# Main.net
KiCad netlist of a schematic drawn in Altium Designer
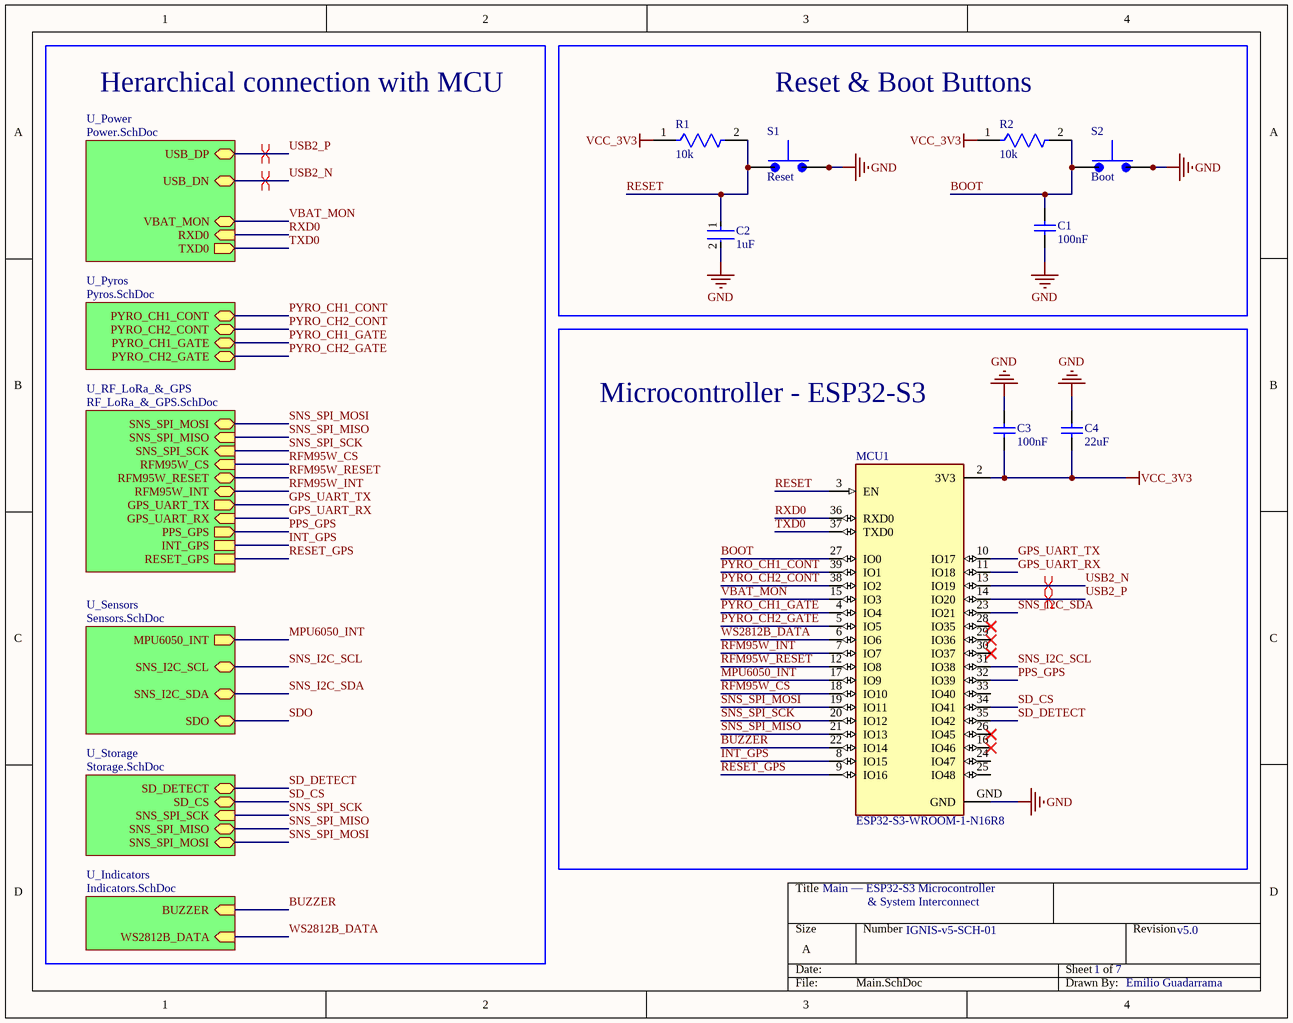
[diagram p0: Main.SchDoc]

(export (version "E")
  (design (tool "Eeschema 10.0.6"))
  (components
    (comp (ref "C1")
      (value "100nF")
      (footprint "CAPC2013X145X50NL20T25")
      (fields (field (name "MANUFACTURER") "Kemet") (field (name "PART NUMBER") "C0805S104K5RACTU"))
      (libsource (lib "Altium Content Vault") (part "CAP"))
    )
    (comp (ref "C2")
      (value "1uF")
      (footprint "FP-0805-L_2_01_0_2-W_1_25-MFG")
      (description "08051C105K4T2A Cap Ceramic 1uF 100V X7R 10% Pad SMD 0805 125C Automotive T/R")
      (fields (field (name "TOLERANCE") "10%"))
      (libsource (lib "Altium Content Vault") (part "b4654b650e69147ec39a6b967a45e02"))
    )
    (comp (ref "C3")
      (value "100nF")
      (footprint "CAPC2013X145X50NL20T25")
      (fields (field (name "MANUFACTURER") "Kemet") (field (name "PART NUMBER") "C0805S104K5RACTU"))
      (libsource (lib "Altium Content Vault") (part "CAP"))
    )
    (comp (ref "C4")
      (value "22uF")
      (footprint "CAPC0805(2012)145_L")
      (description "CAP 22uF 6.3V ±10% 0805 (2012 Metric) Thickness 1.45mm SMD")
      (fields (field (name "TOLERANCE") "Â±10%"))
      (libsource (lib "Altium Content Vault") (part "CAP"))
    )
    (comp (ref "MCU1")
      (value "ESP32-S3-WROOM-1-N16R8")
      (footprint "XCVR_ESP32-S3-WROOM-1-N16R2")
      (description "Bluetooth, WiFi 802.11b/g/n, Bluetooth v5.0 Transceiver Module 2.4GHz PCB Trace Surface Mount")
      (fields (field (name "MF") "Espressif Systems") (field (name "MP") "ESP32S3WROOM1N16R2"))
      (libsource (lib "ESP32-S3-WROOM-1-N16R8") (part "ESP32-S3-WROOM-1-N16R8"))
    )
    (comp (ref "R1")
      (value "10k")
      (footprint "FP-MCT0603-IPC_A")
      (description "RES SMD 100 OHM 1% 1/8W 0603")
      (fields (field (name "TOLERANCE") "0.1%"))
      (libsource (lib "Altium Content Vault") (part "1029c3af85768c4190bb7ad29bc67b5"))
    )
    (comp (ref "R2")
      (value "10k")
      (footprint "FP-MCT0603-IPC_A")
      (description "RES SMD 100 OHM 1% 1/8W 0603")
      (fields (field (name "TOLERANCE") "0.1%"))
      (libsource (lib "Altium Content Vault") (part "1029c3af85768c4190bb7ad29bc67b5"))
    )
    (comp (ref "S1")
      (value "Reset")
      (footprint "SW_SKRPABE010")
      (description "Switch Tactile N.O. SPST Button J-Bend 0.05A 16VDC 1.57N SMD Automotive T/R")
      (fields (field (name "MF") "ALPS") (field (name "MP") "SKRPABE010"))
      (libsource (lib "SKRPABE010") (part "SKRPABE010"))
    )
    (comp (ref "S2")
      (value "Boot")
      (footprint "SW_SKRPABE010")
      (description "Switch Tactile N.O. SPST Button J-Bend 0.05A 16VDC 1.57N SMD Automotive T/R")
      (fields (field (name "MF") "ALPS") (field (name "MP") "SKRPABE010"))
      (libsource (lib "SKRPABE010") (part "SKRPABE010"))
    )
  )
  (nets
    (net (code "2") (name "/BOOT") (class "Default")
      (node (ref "C1") (pin "2") (pinfunction "2_2") (pintype "passive"))
      (node (ref "MCU1") (pin "27") (pinfunction "IO0_27") (pintype "bidirectional"))
      (node (ref "R2") (pin "2") (pinfunction "2_2") (pintype "passive"))
      (node (ref "S2") (pin "1") (pinfunction "1_1") (pintype "passive"))
      (node (ref "S2") (pin "2") (pinfunction "1_2") (pintype "passive"))
    )
    (net (code "3") (name "/BUZZER") (class "Default")
      (node (ref "MCU1") (pin "22") (pinfunction "IO14_22") (pintype "bidirectional"))
    )
    (net (code "4") (name "/GPS_UART_RX") (class "Default")
      (node (ref "MCU1") (pin "11") (pinfunction "IO18_11") (pintype "bidirectional"))
    )
    (net (code "5") (name "/GPS_UART_TX") (class "Default")
      (node (ref "MCU1") (pin "10") (pinfunction "IO17_10") (pintype "bidirectional"))
    )
    (net (code "6") (name "/INT_GPS") (class "Default")
      (node (ref "MCU1") (pin "8") (pinfunction "IO15_8") (pintype "bidirectional"))
    )
    (net (code "7") (name "/MPU6050_INT") (class "Default")
      (node (ref "MCU1") (pin "17") (pinfunction "IO9_17") (pintype "bidirectional"))
    )
    (net (code "8") (name "/PPS_GPS") (class "Default")
      (node (ref "MCU1") (pin "32") (pinfunction "IO39_32") (pintype "bidirectional"))
    )
    (net (code "9") (name "/PYRO_CH1_CONT") (class "Default")
      (node (ref "MCU1") (pin "39") (pinfunction "IO1_39") (pintype "bidirectional"))
    )
    (net (code "10") (name "/PYRO_CH1_GATE") (class "Default")
      (node (ref "MCU1") (pin "4") (pinfunction "IO4_4") (pintype "bidirectional"))
    )
    (net (code "11") (name "/PYRO_CH2_CONT") (class "Default")
      (node (ref "MCU1") (pin "38") (pinfunction "IO2_38") (pintype "bidirectional"))
    )
    (net (code "12") (name "/PYRO_CH2_GATE") (class "Default")
      (node (ref "MCU1") (pin "5") (pinfunction "IO5_5") (pintype "bidirectional"))
    )
    (net (code "13") (name "/RESET") (class "Default")
      (node (ref "C2") (pin "1") (pinfunction "1_1") (pintype "passive"))
      (node (ref "MCU1") (pin "3") (pinfunction "EN_3") (pintype "input"))
      (node (ref "R1") (pin "2") (pinfunction "2_2") (pintype "passive"))
      (node (ref "S1") (pin "1") (pinfunction "1_1") (pintype "passive"))
      (node (ref "S1") (pin "2") (pinfunction "1_2") (pintype "passive"))
    )
    (net (code "14") (name "/RESET_GPS") (class "Default")
      (node (ref "MCU1") (pin "9") (pinfunction "IO16_9") (pintype "bidirectional"))
    )
    (net (code "15") (name "/RFM95W_CS") (class "Default")
      (node (ref "MCU1") (pin "18") (pinfunction "IO10_18") (pintype "bidirectional"))
    )
    (net (code "16") (name "/RFM95W_INT") (class "Default")
      (node (ref "MCU1") (pin "7") (pinfunction "IO7_7") (pintype "bidirectional"))
    )
    (net (code "17") (name "/RFM95W_RESET") (class "Default")
      (node (ref "MCU1") (pin "12") (pinfunction "IO8_12") (pintype "bidirectional"))
    )
    (net (code "18") (name "/RXD0") (class "Default")
      (node (ref "MCU1") (pin "36") (pinfunction "RXD0_36") (pintype "bidirectional"))
    )
    (net (code "20") (name "/SD_CS") (class "Default")
      (node (ref "MCU1") (pin "34") (pinfunction "IO41_34") (pintype "bidirectional"))
    )
    (net (code "21") (name "/SD_DETECT") (class "Default")
      (node (ref "MCU1") (pin "35") (pinfunction "IO42_35") (pintype "bidirectional"))
    )
    (net (code "22") (name "/SNS_I2C_SCL") (class "Default")
      (node (ref "MCU1") (pin "31") (pinfunction "IO38_31") (pintype "bidirectional"))
    )
    (net (code "23") (name "/SNS_I2C_SDA") (class "Default")
      (node (ref "MCU1") (pin "23") (pinfunction "IO21_23") (pintype "bidirectional"))
    )
    (net (code "24") (name "/SNS_SPI_MISO") (class "Default")
      (node (ref "MCU1") (pin "21") (pinfunction "IO13_21") (pintype "bidirectional"))
    )
    (net (code "25") (name "/SNS_SPI_MOSI") (class "Default")
      (node (ref "MCU1") (pin "19") (pinfunction "IO11_19") (pintype "bidirectional"))
    )
    (net (code "26") (name "/SNS_SPI_SCK") (class "Default")
      (node (ref "MCU1") (pin "20") (pinfunction "IO12_20") (pintype "bidirectional"))
    )
    (net (code "27") (name "/TXD0") (class "Default")
      (node (ref "MCU1") (pin "37") (pinfunction "TXD0_37") (pintype "bidirectional"))
    )
    (net (code "28") (name "/USB2_N") (class "Default")
      (node (ref "MCU1") (pin "13") (pinfunction "IO19_13") (pintype "bidirectional"))
    )
    (net (code "29") (name "/USB2_P") (class "Default")
      (node (ref "MCU1") (pin "14") (pinfunction "IO20_14") (pintype "bidirectional"))
    )
    (net (code "30") (name "/VBAT_MON") (class "Default")
      (node (ref "MCU1") (pin "15") (pinfunction "IO3_15") (pintype "bidirectional"))
    )
    (net (code "31") (name "/WS2812B_DATA") (class "Default")
      (node (ref "MCU1") (pin "6") (pinfunction "IO6_6") (pintype "bidirectional"))
    )
    (net (code "32") (name "GND") (class "Default")
      (node (ref "C1") (pin "1") (pinfunction "1_1") (pintype "passive"))
      (node (ref "C2") (pin "2") (pinfunction "2_2") (pintype "passive"))
      (node (ref "C3") (pin "2") (pinfunction "2_2") (pintype "passive"))
      (node (ref "C4") (pin "2") (pinfunction "2_2") (pintype "passive"))
      (node (ref "MCU1") (pin "GND") (pinfunction "GND_GND") (pintype "power_in"))
      (node (ref "S1") (pin "3") (pinfunction "2_3") (pintype "passive"))
      (node (ref "S1") (pin "4") (pinfunction "2_4") (pintype "passive"))
      (node (ref "S2") (pin "3") (pinfunction "2_3") (pintype "passive"))
      (node (ref "S2") (pin "4") (pinfunction "2_4") (pintype "passive"))
    )
    (net (code "33") (name "VCC_3V3") (class "Default")
      (node (ref "C3") (pin "1") (pinfunction "1_1") (pintype "passive"))
      (node (ref "C4") (pin "1") (pinfunction "1_1") (pintype "passive"))
      (node (ref "MCU1") (pin "2") (pinfunction "3V3_2") (pintype "power_in"))
      (node (ref "R1") (pin "1") (pinfunction "1_1") (pintype "passive"))
      (node (ref "R2") (pin "1") (pinfunction "1_1") (pintype "passive"))
    )
    (net (code "34") (name "unconnected-(MCU1-IO35-Pad28)") (class "Default")
      (node (ref "MCU1") (pin "28") (pinfunction "IO35_28") (pintype "bidirectional+no_connect"))
    )
    (net (code "35") (name "unconnected-(MCU1-IO36-Pad29)") (class "Default")
      (node (ref "MCU1") (pin "29") (pinfunction "IO36_29") (pintype "bidirectional+no_connect"))
    )
    (net (code "36") (name "unconnected-(MCU1-IO37-Pad30)") (class "Default")
      (node (ref "MCU1") (pin "30") (pinfunction "IO37_30") (pintype "bidirectional+no_connect"))
    )
    (net (code "37") (name "unconnected-(MCU1-IO40-Pad33)") (class "Default")
      (node (ref "MCU1") (pin "33") (pinfunction "IO40_33") (pintype "bidirectional"))
    )
    (net (code "38") (name "unconnected-(MCU1-IO45-Pad26)") (class "Default")
      (node (ref "MCU1") (pin "26") (pinfunction "IO45_26") (pintype "bidirectional+no_connect"))
    )
    (net (code "39") (name "unconnected-(MCU1-IO46-Pad16)") (class "Default")
      (node (ref "MCU1") (pin "16") (pinfunction "IO46_16") (pintype "bidirectional+no_connect"))
    )
    (net (code "40") (name "unconnected-(MCU1-IO47-Pad24)") (class "Default")
      (node (ref "MCU1") (pin "24") (pinfunction "IO47_24") (pintype "bidirectional"))
    )
    (net (code "41") (name "unconnected-(MCU1-IO48-Pad25)") (class "Default")
      (node (ref "MCU1") (pin "25") (pinfunction "IO48_25") (pintype "bidirectional"))
    )
  )
)
